# design.net
KiCad netlist of a schematic drawn in EasyEDA Pro
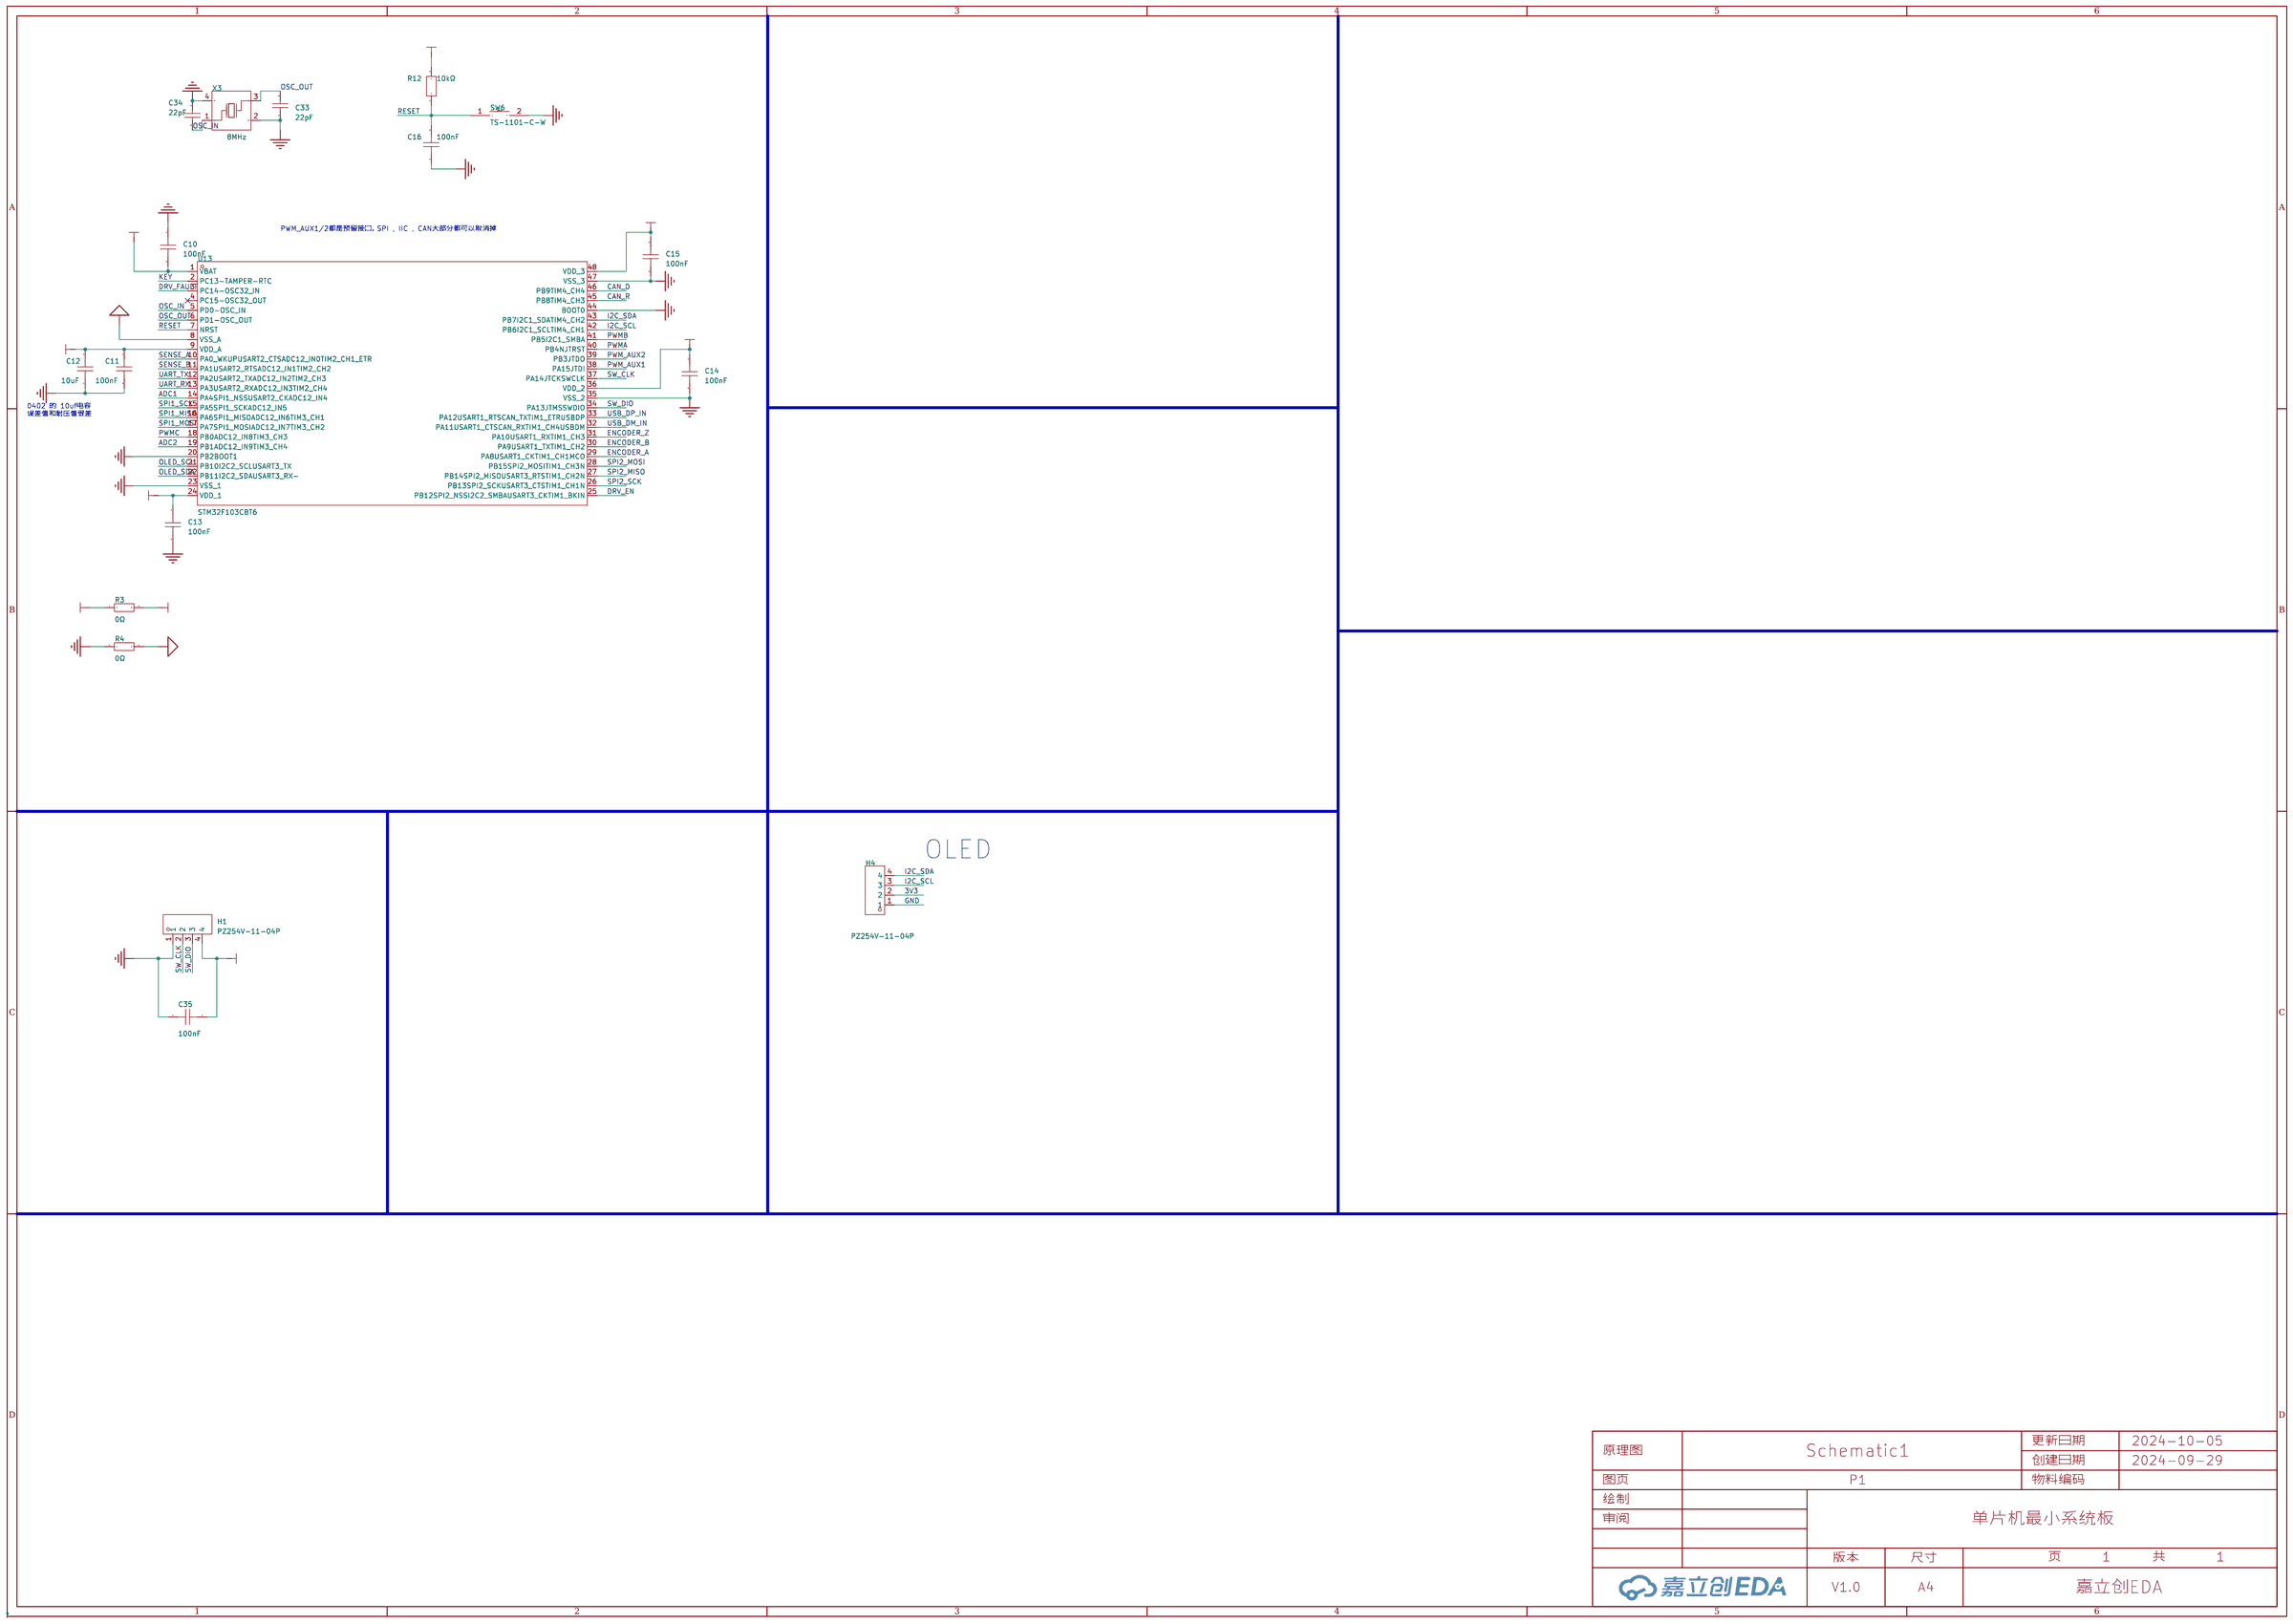
[diagram p0: schematic sheet]

(export (version "E")
  (design (tool "Eeschema 10.0.6"))
  (components
    (comp (ref "C10")
      (value "100nF")
      (footprint "easyedapro:C0603")
      (description "容值:100nF;精度:±10%;额定电压:50V;材质(温度系数):X7R;")
      (fields
        (field (name "Manufacturer Part") "CGA0603X7R104K500JT")
        (field (name "Manufacturer") "HRE(芯声)")
      )
      (libsource (lib "easyedapro") (part "CGA0603X7R104K500JT"))
    )
    (comp (ref "C11")
      (value "100nF")
      (footprint "easyedapro:C0603")
      (description "容值:100nF;精度:±10%;额定电压:50V;材质(温度系数):X7R;")
      (fields
        (field (name "Manufacturer Part") "CGA0603X7R104K500JT")
        (field (name "Manufacturer") "HRE(芯声)")
      )
      (libsource (lib "easyedapro") (part "CGA0603X7R104K500JT"))
    )
    (comp (ref "C12")
      (value "10uF")
      (footprint "easyedapro:C0603")
      (description "容值:10uF;精度:±20%;额定电压:35V;材质(温度系数):X5R;")
      (fields
        (field (name "Manufacturer Part") "GRM188R6YA106MA73D")
        (field (name "Manufacturer") "muRata(村田)")
      )
      (libsource (lib "easyedapro") (part "GRM188R6YA106MA73D"))
    )
    (comp (ref "C13")
      (value "100nF")
      (footprint "easyedapro:C0603")
      (description "容值:100nF;精度:±10%;额定电压:50V;材质(温度系数):X7R;")
      (fields
        (field (name "Manufacturer Part") "CGA0603X7R104K500JT")
        (field (name "Manufacturer") "HRE(芯声)")
      )
      (libsource (lib "easyedapro") (part "CGA0603X7R104K500JT"))
    )
    (comp (ref "C14")
      (value "100nF")
      (footprint "easyedapro:C0603")
      (description "容值:100nF;精度:±10%;额定电压:50V;材质(温度系数):X7R;")
      (fields
        (field (name "Manufacturer Part") "CGA0603X7R104K500JT")
        (field (name "Manufacturer") "HRE(芯声)")
      )
      (libsource (lib "easyedapro") (part "CGA0603X7R104K500JT"))
    )
    (comp (ref "C15")
      (value "100nF")
      (footprint "easyedapro:C0603")
      (description "容值:100nF;精度:±10%;额定电压:50V;材质(温度系数):X7R;")
      (fields
        (field (name "Manufacturer Part") "CGA0603X7R104K500JT")
        (field (name "Manufacturer") "HRE(芯声)")
      )
      (libsource (lib "easyedapro") (part "CGA0603X7R104K500JT"))
    )
    (comp (ref "C16")
      (value "100nF")
      (footprint "easyedapro:C0603")
      (description "容值:100nF;精度:±10%;额定电压:50V;材质(温度系数):X7R;")
      (fields
        (field (name "Manufacturer Part") "CGA0603X7R104K500JT")
        (field (name "Manufacturer") "HRE(芯声)")
      )
      (libsource (lib "easyedapro") (part "CGA0603X7R104K500JT"))
    )
    (comp (ref "C33")
      (value "22pF")
      (footprint "easyedapro:C0603")
      (description "容值:22pF;精度:±5%;额定电压:50V;材质(温度系数):C0G;")
      (fields
        (field (name "Manufacturer Part") "CL10C220JB8NNNC")
        (field (name "Manufacturer") "SAMSUNG(三星)")
      )
      (libsource (lib "easyedapro") (part "CL10C220JB8NNNC"))
    )
    (comp (ref "C34")
      (value "22pF")
      (footprint "easyedapro:C0603")
      (description "容值:22pF;精度:±5%;额定电压:50V;材质(温度系数):C0G;")
      (fields
        (field (name "Manufacturer Part") "CL10C220JB8NNNC")
        (field (name "Manufacturer") "SAMSUNG(三星)")
      )
      (libsource (lib "easyedapro") (part "CL10C220JB8NNNC"))
    )
    (comp (ref "C35")
      (value "100nF")
      (footprint "easyedapro:C0603")
      (description "容值:100nF;精度:±10%;额定电压:50V;材质(温度系数):X7R;")
      (fields
        (field (name "Manufacturer Part") "CGA0603X7R104K500JT")
        (field (name "Manufacturer") "HRE(芯声)")
      )
      (libsource (lib "easyedapro") (part "CGA0603X7R104K500JT"))
    )
    (comp (ref "H1")
      (value "PZ254V-11-04P")
      (footprint "easyedapro:HDR-TH_4P-P2.54-V-M")
      (fields (field (name "Manufacturer") "XFCN(兴飞)"))
      (libsource (lib "easyedapro") (part "PZ254V-11-04P_C2691448"))
    )
    (comp (ref "H4")
      (value "PZ254V-11-04P")
      (footprint "easyedapro:HDR-TH_4P-P2.54-V-M")
      (fields (field (name "Manufacturer") "XFCN(兴飞)"))
      (libsource (lib "easyedapro") (part "PZ254V-11-04P_C2691448"))
    )
    (comp (ref "R3")
      (value "0Ω")
      (footprint "easyedapro:R0603")
      (description "电阻类型:厚膜电阻;阻值:0Ω;精度:±1%;功率:100mW;最大工作电压:75V;")
      (fields
        (field (name "Manufacturer Part") "0603WAF0000T5E")
        (field (name "Manufacturer") "UNI-ROYAL(厚声)")
      )
      (libsource (lib "easyedapro") (part "0603WAF0000T5E"))
    )
    (comp (ref "R4")
      (value "0Ω")
      (footprint "easyedapro:R0603")
      (description "电阻类型:厚膜电阻;阻值:0Ω;精度:±1%;功率:100mW;最大工作电压:75V;")
      (fields
        (field (name "Manufacturer Part") "0603WAF0000T5E")
        (field (name "Manufacturer") "UNI-ROYAL(厚声)")
      )
      (libsource (lib "easyedapro") (part "0603WAF0000T5E"))
    )
    (comp (ref "R12")
      (value "10kΩ")
      (footprint "easyedapro:R0603")
      (description "电阻类型:厚膜电阻;阻值:10kΩ;精度:±5%;功率:100mW;最大工作电压:75V;温度系数:±100ppm/°C;")
      (fields (field (name "Manufacturer Part") "FRC0603J103TS") (field (name "Manufacturer") "FOJAN(富捷)"))
      (libsource (lib "easyedapro") (part "FRC0603J103TS"))
    )
    (comp (ref "SW6")
      (value "TS-1101-C-W")
      (footprint "easyedapro:SW-SMD_L6.0-W3.3-LS8.0")
      (fields (field (name "Manufacturer") "XKB Connectivity(中国星坤)"))
      (libsource (lib "easyedapro") (part "TS-1101-C-W"))
    )
    (comp (ref "U13")
      (value "STM32F103CBT6")
      (footprint "easyedapro:LQFP-48_L7.0-W7.0-P0.50-LS9.0-BL")
      (description "CPU内核:ARM-M3;程序存储容量:128KB;RAM总容量:20KB;GPIO端口数量:37;工作电压范围:2V~3.6V;CPU最大主频:72MHz;程序存储器类型:FLASH;")
      (fields (field (name "Manufacturer") "ST(意法半导体)"))
      (libsource (lib "easyedapro") (part "STM32F103CBT6"))
    )
    (comp (ref "X3")
      (value "8MHz")
      (footprint "easyedapro:OSC-SMD_4P-L3.2-W2.5-BL")
      (description "晶振类型:贴片晶振;频率:8MHz;常温频差:±20ppm;外接负载电容:12pF;频率稳定度(全温):±20ppm;")
      (fields (field (name "Manufacturer Part") "TAXM8M4RFDCET2T") (field (name "Manufacturer") "YJX(雅晶鑫)"))
      (libsource (lib "easyedapro") (part "TAXM8M4RFDCET2T"))
    )
  )
  (nets
    (net (code "1") (name "/ADC1") (class "Default")
      (node (ref "U13") (pin "14") (pinfunction "PA4SPI1_NSSUSART2_CKADC12_IN4_14") (pintype "unspecified"))
    )
    (net (code "2") (name "/ADC2") (class "Default")
      (node (ref "U13") (pin "19") (pinfunction "PB1ADC12_IN9TIM3_CH4_19") (pintype "unspecified"))
    )
    (net (code "3") (name "/CAN_D") (class "Default")
      (node (ref "U13") (pin "46") (pinfunction "PB9TIM4_CH4_46") (pintype "unspecified"))
    )
    (net (code "4") (name "/CAN_R") (class "Default")
      (node (ref "U13") (pin "45") (pinfunction "PB8TIM4_CH3_45") (pintype "unspecified"))
    )
    (net (code "5") (name "/DRV_EN") (class "Default")
      (node (ref "U13") (pin "25") (pinfunction "PB12SPI2_NSSI2C2_SMBAUSART3_CKTIM1_BKIN_25") (pintype "unspecified"))
    )
    (net (code "6") (name "/DRV_FAULT") (class "Default")
      (node (ref "U13") (pin "3") (pinfunction "PC14-OSC32_IN_3") (pintype "unspecified"))
    )
    (net (code "7") (name "/ENCODER_A") (class "Default")
      (node (ref "U13") (pin "29") (pinfunction "PA8USART1_CKTIM1_CH1MCO_29") (pintype "unspecified"))
    )
    (net (code "8") (name "/ENCODER_B") (class "Default")
      (node (ref "U13") (pin "30") (pinfunction "PA9USART1_TXTIM1_CH2_30") (pintype "unspecified"))
    )
    (net (code "9") (name "/ENCODER_Z") (class "Default")
      (node (ref "U13") (pin "31") (pinfunction "PA10USART1_RXTIM1_CH3_31") (pintype "unspecified"))
    )
    (net (code "10") (name "/I2C_SCL") (class "Default")
      (node (ref "H4") (pin "3") (pinfunction "3_3") (pintype "unspecified"))
      (node (ref "U13") (pin "42") (pinfunction "PB6I2C1_SCLTIM4_CH1_42") (pintype "unspecified"))
    )
    (net (code "11") (name "/I2C_SDA") (class "Default")
      (node (ref "H4") (pin "4") (pinfunction "4_4") (pintype "unspecified"))
      (node (ref "U13") (pin "43") (pinfunction "PB7I2C1_SDATIM4_CH2_43") (pintype "unspecified"))
    )
    (net (code "12") (name "/KEY") (class "Default")
      (node (ref "U13") (pin "2") (pinfunction "PC13-TAMPER-RTC_2") (pintype "unspecified"))
    )
    (net (code "13") (name "/OLED_SCL") (class "Default")
      (node (ref "U13") (pin "21") (pinfunction "PB10I2C2_SCLUSART3_TX_21") (pintype "unspecified"))
    )
    (net (code "14") (name "/OLED_SDA") (class "Default")
      (node (ref "U13") (pin "22") (pinfunction "PB11I2C2_SDAUSART3_RX-_22") (pintype "unspecified"))
    )
    (net (code "15") (name "/OSC_IN") (class "Default")
      (node (ref "C34") (pin "2") (pinfunction "2_2") (pintype "input"))
      (node (ref "U13") (pin "5") (pinfunction "PD0-OSC_IN_5") (pintype "unspecified"))
      (node (ref "X3") (pin "1") (pinfunction "OSC1_1") (pintype "unspecified"))
    )
    (net (code "16") (name "/OSC_OUT") (class "Default")
      (node (ref "C33") (pin "2") (pinfunction "2_2") (pintype "input"))
      (node (ref "U13") (pin "6") (pinfunction "PD1-OSC_OUT_6") (pintype "unspecified"))
      (node (ref "X3") (pin "3") (pinfunction "OSC2_3") (pintype "unspecified"))
    )
    (net (code "17") (name "/PWMA") (class "Default")
      (node (ref "U13") (pin "40") (pinfunction "PB4NJTRST_40") (pintype "unspecified"))
    )
    (net (code "18") (name "/PWMB") (class "Default")
      (node (ref "U13") (pin "41") (pinfunction "PB5I2C1_SMBA_41") (pintype "unspecified"))
    )
    (net (code "19") (name "/PWMC") (class "Default")
      (node (ref "U13") (pin "18") (pinfunction "PB0ADC12_IN8TIM3_CH3_18") (pintype "unspecified"))
    )
    (net (code "20") (name "/PWM_AUX1") (class "Default")
      (node (ref "U13") (pin "38") (pinfunction "PA15JTDI_38") (pintype "unspecified"))
    )
    (net (code "21") (name "/PWM_AUX2") (class "Default")
      (node (ref "U13") (pin "39") (pinfunction "PB3JTDO_39") (pintype "unspecified"))
    )
    (net (code "22") (name "/RESET") (class "Default")
      (node (ref "C16") (pin "2") (pinfunction "2_2") (pintype "unspecified"))
      (node (ref "R12") (pin "1") (pinfunction "1_1") (pintype "unspecified"))
      (node (ref "SW6") (pin "1") (pinfunction "1_1") (pintype "unspecified"))
      (node (ref "U13") (pin "7") (pinfunction "NRST_7") (pintype "unspecified"))
    )
    (net (code "23") (name "/SENSE_A") (class "Default")
      (node (ref "U13") (pin "10") (pinfunction "PA0_WKUPUSART2_CTSADC12_IN0TIM2_CH1_ETR_10") (pintype "unspecified"))
    )
    (net (code "24") (name "/SENSE_B") (class "Default")
      (node (ref "U13") (pin "11") (pinfunction "PA1USART2_RTSADC12_IN1TIM2_CH2_11") (pintype "unspecified"))
    )
    (net (code "25") (name "/SPI1_MISO") (class "Default")
      (node (ref "U13") (pin "16") (pinfunction "PA6SPI1_MISOADC12_IN6TIM3_CH1_16") (pintype "unspecified"))
    )
    (net (code "26") (name "/SPI1_MOSI") (class "Default")
      (node (ref "U13") (pin "17") (pinfunction "PA7SPI1_MOSIADC12_IN7TIM3_CH2_17") (pintype "unspecified"))
    )
    (net (code "27") (name "/SPI1_SCK") (class "Default")
      (node (ref "U13") (pin "15") (pinfunction "PA5SPI1_SCKADC12_IN5_15") (pintype "unspecified"))
    )
    (net (code "28") (name "/SPI2_MISO") (class "Default")
      (node (ref "U13") (pin "27") (pinfunction "PB14SPI2_MISOUSART3_RTSTIM1_CH2N_27") (pintype "unspecified"))
    )
    (net (code "29") (name "/SPI2_MOSI") (class "Default")
      (node (ref "U13") (pin "28") (pinfunction "PB15SPI2_MOSITIM1_CH3N_28") (pintype "unspecified"))
    )
    (net (code "30") (name "/SPI2_SCK") (class "Default")
      (node (ref "U13") (pin "26") (pinfunction "PB13SPI2_SCKUSART3_CTSTIM1_CH1N_26") (pintype "unspecified"))
    )
    (net (code "31") (name "/SW_CLK") (class "Default")
      (node (ref "H1") (pin "2") (pinfunction "2_2") (pintype "unspecified"))
      (node (ref "U13") (pin "37") (pinfunction "PA14JTCKSWCLK_37") (pintype "unspecified"))
    )
    (net (code "32") (name "/SW_DIO") (class "Default")
      (node (ref "H1") (pin "3") (pinfunction "3_3") (pintype "unspecified"))
      (node (ref "U13") (pin "34") (pinfunction "PA13JTMSSWDIO_34") (pintype "unspecified"))
    )
    (net (code "33") (name "/UART_RX") (class "Default")
      (node (ref "U13") (pin "13") (pinfunction "PA3USART2_RXADC12_IN3TIM2_CH4_13") (pintype "unspecified"))
    )
    (net (code "34") (name "/UART_TX") (class "Default")
      (node (ref "U13") (pin "12") (pinfunction "PA2USART2_TXADC12_IN2TIM2_CH3_12") (pintype "unspecified"))
    )
    (net (code "35") (name "/USB_DM_IN") (class "Default")
      (node (ref "U13") (pin "32") (pinfunction "PA11USART1_CTSCAN_RXTIM1_CH4USBDM_32") (pintype "unspecified"))
    )
    (net (code "36") (name "/USB_DP_IN") (class "Default")
      (node (ref "U13") (pin "33") (pinfunction "PA12USART1_RTSCAN_TXTIM1_ETRUSBDP_33") (pintype "unspecified"))
    )
    (net (code "37") (name "3V3") (class "Default")
      (node (ref "C10") (pin "2") (pinfunction "2_2") (pintype "unspecified"))
      (node (ref "C13") (pin "1") (pinfunction "1_1") (pintype "unspecified"))
      (node (ref "C14") (pin "1") (pinfunction "1_1") (pintype "unspecified"))
      (node (ref "C15") (pin "1") (pinfunction "1_1") (pintype "unspecified"))
      (node (ref "C35") (pin "2") (pinfunction "2_2") (pintype "unspecified"))
      (node (ref "H1") (pin "4") (pinfunction "4_4") (pintype "unspecified"))
      (node (ref "H4") (pin "2") (pinfunction "2_2") (pintype "unspecified"))
      (node (ref "R12") (pin "2") (pinfunction "2_2") (pintype "unspecified"))
      (node (ref "R3") (pin "1") (pinfunction "1_1") (pintype "input"))
      (node (ref "U13") (pin "1") (pinfunction "VBAT_1") (pintype "unspecified"))
      (node (ref "U13") (pin "24") (pinfunction "VDD_1_24") (pintype "unspecified"))
      (node (ref "U13") (pin "36") (pinfunction "VDD_2_36") (pintype "unspecified"))
      (node (ref "U13") (pin "48") (pinfunction "VDD_3_48") (pintype "unspecified"))
    )
    (net (code "38") (name "AGND") (class "Default")
      (node (ref "R4") (pin "2") (pinfunction "2_2") (pintype "input"))
      (node (ref "U13") (pin "8") (pinfunction "VSS_A_8") (pintype "unspecified"))
    )
    (net (code "39") (name "AVCC") (class "Default")
      (node (ref "C11") (pin "1") (pinfunction "1_1") (pintype "unspecified"))
      (node (ref "C12") (pin "2") (pinfunction "2_2") (pintype "input"))
      (node (ref "R3") (pin "2") (pinfunction "2_2") (pintype "input"))
      (node (ref "U13") (pin "9") (pinfunction "VDD_A_9") (pintype "unspecified"))
    )
    (net (code "40") (name "GND") (class "Default")
      (node (ref "C10") (pin "1") (pinfunction "1_1") (pintype "unspecified"))
      (node (ref "C11") (pin "2") (pinfunction "2_2") (pintype "unspecified"))
      (node (ref "C12") (pin "1") (pinfunction "1_1") (pintype "input"))
      (node (ref "C13") (pin "2") (pinfunction "2_2") (pintype "unspecified"))
      (node (ref "C14") (pin "2") (pinfunction "2_2") (pintype "unspecified"))
      (node (ref "C15") (pin "2") (pinfunction "2_2") (pintype "unspecified"))
      (node (ref "C16") (pin "1") (pinfunction "1_1") (pintype "unspecified"))
      (node (ref "C33") (pin "1") (pinfunction "1_1") (pintype "input"))
      (node (ref "C34") (pin "1") (pinfunction "1_1") (pintype "input"))
      (node (ref "C35") (pin "1") (pinfunction "1_1") (pintype "unspecified"))
      (node (ref "H1") (pin "1") (pinfunction "1_1") (pintype "unspecified"))
      (node (ref "H4") (pin "1") (pinfunction "1_1") (pintype "unspecified"))
      (node (ref "R4") (pin "1") (pinfunction "1_1") (pintype "input"))
      (node (ref "SW6") (pin "2") (pinfunction "2_2") (pintype "unspecified"))
      (node (ref "U13") (pin "20") (pinfunction "PB2BOOT1_20") (pintype "unspecified"))
      (node (ref "U13") (pin "23") (pinfunction "VSS_1_23") (pintype "unspecified"))
      (node (ref "U13") (pin "35") (pinfunction "VSS_2_35") (pintype "unspecified"))
      (node (ref "U13") (pin "44") (pinfunction "BOOT0_44") (pintype "unspecified"))
      (node (ref "U13") (pin "47") (pinfunction "VSS_3_47") (pintype "unspecified"))
      (node (ref "X3") (pin "2") (pinfunction "GND_2") (pintype "unspecified"))
      (node (ref "X3") (pin "4") (pinfunction "GND_4") (pintype "unspecified"))
    )
    (net (code "41") (name "unconnected-(U13-PC15-OSC32_OUT-Pad4)") (class "Default")
      (node (ref "U13") (pin "4") (pinfunction "PC15-OSC32_OUT_4") (pintype "unspecified+no_connect"))
    )
  )
)
